# Source.net
KiCad netlist of a schematic drawn in Altium Designer
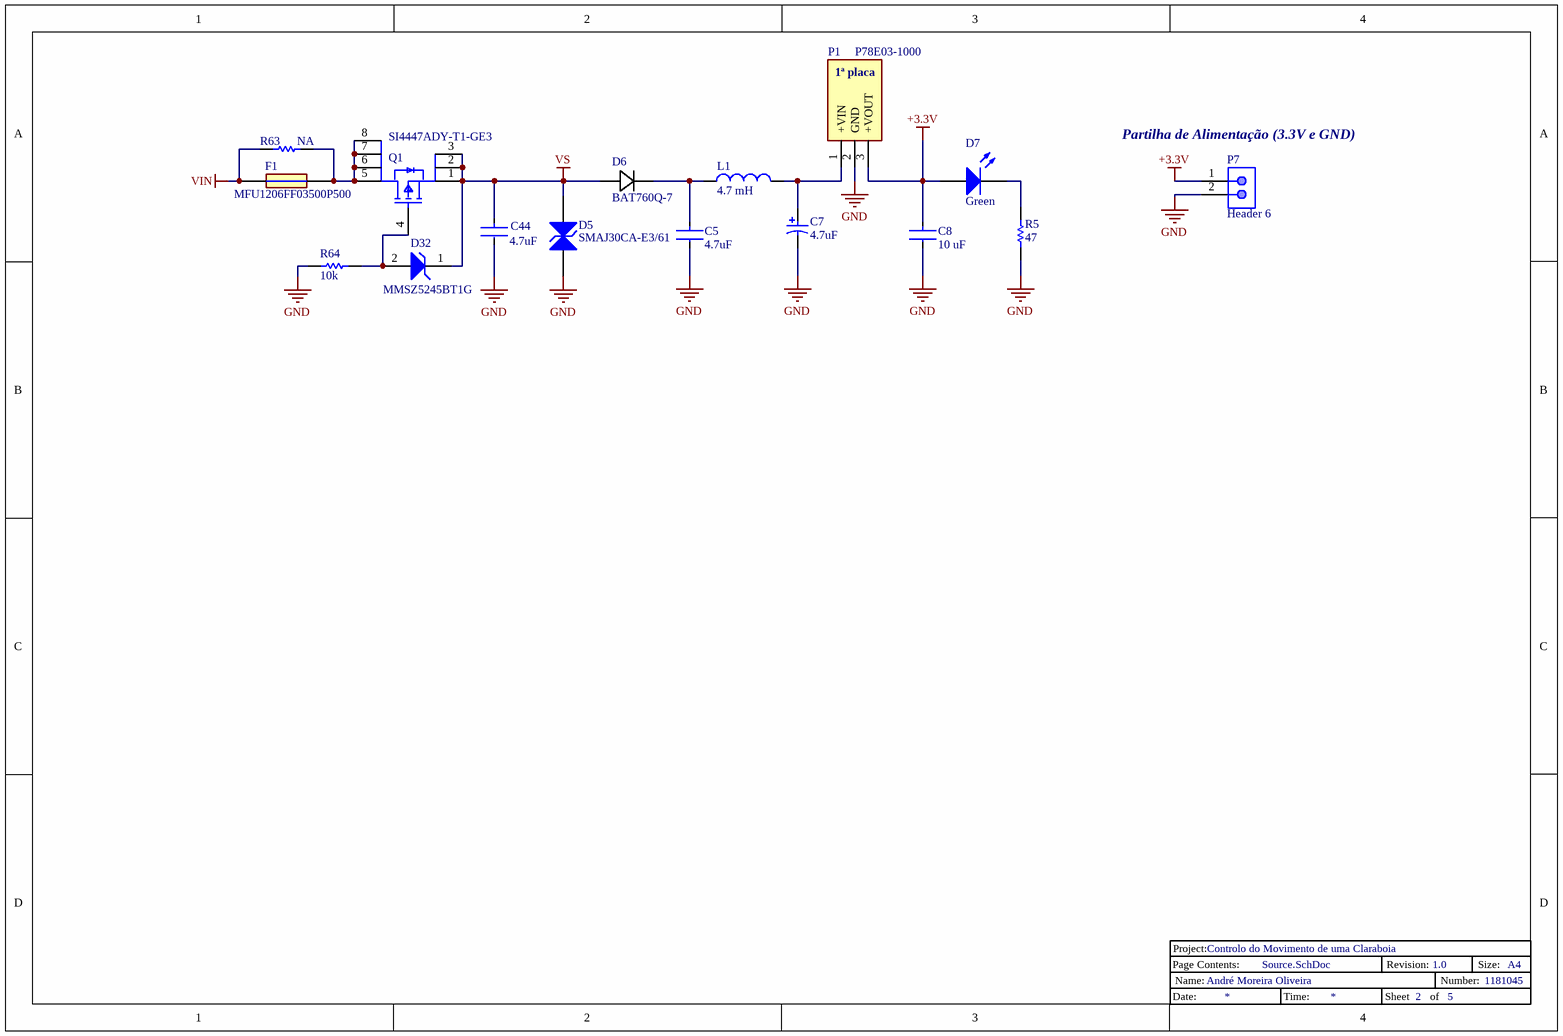
[diagram p0: Source.SchDoc]

(export (version "E")
  (design (tool "Eeschema 10.0.6"))
  (components
    (comp (ref "C5")
      (value "4.7uF")
      (footprint "FP-GRT21B-0_15-IPC_B")
      (description "Cap Ceramic 4.7uF 50V X5R ±10% SMD 0805 +85°C Emboss T/R")
      (fields (field (name "TOLERANCE") "10%"))
      (libsource (lib "Altium Content Vault") (part "11868f565c42a9108669ba33697ecf6"))
    )
    (comp (ref "C7")
      (value "4.7uF")
      (footprint "KEMT-T491-D_L")
      (fields (field (name "VOLTAGE") "50VDC") (field (name "MANUFACTURER") "Kemet"))
      (libsource (lib "Altium Content Vault") (part "CAP-P-2"))
    )
    (comp (ref "C8")
      (value "10 uF")
      (footprint "FP-GRM21B-0_2-e0_2_0_7-IPC_C")
      (libsource (lib "Altium Content Vault") (part "b4654b650e69147ec39a6b967a45e02"))
    )
    (comp (ref "C44")
      (value "4.7uF")
      (footprint "FP-GRT21B-0_15-IPC_B")
      (description "Cap Ceramic 4.7uF 50V X5R ±10% SMD 0805 +85°C Emboss T/R")
      (fields (field (name "TOLERANCE") "10%"))
      (libsource (lib "Altium Content Vault") (part "11868f565c42a9108669ba33697ecf6"))
    )
    (comp (ref "D5")
      (value "SMAJ30CA-E3/61")
      (footprint "VISH-DO-214AC-2_L")
      (fields (field (name "MANUFACTURER") "Vishay Semiconductor"))
      (libsource (lib "Altium Content Vault") (part "VISH-A1A2-2"))
    )
    (comp (ref "D6")
      (value "BAT760Q-7")
      (footprint "DIODE_SOD-323_1P7X1P3_DIO-L")
      (description "No Description Available")
      (fields (field (name "COPYRIGHT") "Copyright (C) 2018 Accelerated Designs. All rights reserved"))
      (libsource (lib "BAT760Q-7") (part "BAT760Q-7"))
    )
    (comp (ref "D7")
      (value "Green")
      (footprint "0805_A")
      (description "SMD mono-color Chip LED, WL-SMCW, Bright Green")
      (fields (field (name "PARTNUMBER") "150080VS75000") (field (name "MANUFACTURER") "Wuerth Elektronik"))
      (libsource (lib "Altium Content Vault") (part "WE-LED_K1A2-2"))
    )
    (comp (ref "D32")
      (value "MMSZ5245BT1G")
      (footprint "ONSC-SOD-123-2-425-04_V")
      (description "Zener Voltage Regulator, 500 mW, 2-Pin SOD-123, Pb-Free, Tape and Reel")
      (fields (field (name "MANUFACTURER") "On Semiconductor"))
      (libsource (lib "Altium Content Vault") (part "ONSC-K1A2-2"))
    )
    (comp (ref "F1")
      (value "MFU1206FF03500P500")
      (footprint "SamacSys:RESC3216X65N")
      (description "Fuse")
      (fields
        (field (name "MANUFACTURER_PART_NUMBER") "MFU1206FF00500P100")
        (field (name "MOUSER PART NUMBER") "594-MFU1206FF00500P1")
      )
      (libsource (lib "*") (part "MFU1206FF00500P100"))
    )
    (comp (ref "L1")
      (value "4.7 mH")
      (footprint "WE-TI-LM")
      (description "Radial Leaded Wire Wound Inductor WE-TI, L = 4700 µH 7447721047")
      (libsource (lib "Altium Content Vault") (part "PAS-IND-INDUCTOR-2"))
    )
    (comp (ref "P1")
      (value "P78E03-1000")
      (footprint "SamacSys:P78E031000")
      (description "Connector")
      (fields (field (name "MOUSER PART NUMBER") "490-P78E03-1000"))
      (libsource (lib "*") (part "P78E03-1000"))
    )
    (comp (ref "P7")
      (value "Header 6")
      (footprint "MOLX-22-27-2021_V")
      (fields (field (name "MANUFACTURER") "Molex") (field (name "PARTNUMBER") "0022272021"))
      (libsource (lib "Altium Content Vault") (part "CN-1P-M-R2"))
    )
    (comp (ref "Q1")
      (value "SI4447ADY-T1-GE3")
      (footprint "FP-C-06527-MFG")
      (description "MOSFET P-CH 40V 7.2A 8SOIC")
      (fields
        (field (name "MANUFACTURER") "Vishay")
        (field (name "OCTOPART") "https://octopart.com/si4447ady-t1-ge3-vishay-44677033")
      )
      (libsource (lib "Altium Content Vault") (part "3e6ef26ae044604f9a28074748c896e"))
    )
    (comp (ref "R5")
      (value "47")
      (footprint "RESC1608X55X30NL20T20")
      (fields (field (name "PART NUMBER") "ERA3AEB470V") (field (name "MANUFACTURER") "Panasonic"))
      (libsource (lib "Altium Content Vault") (part "RES"))
    )
    (comp (ref "R63")
      (value "NA")
      (footprint "RESC1608X55X25ML10T15")
      (description "Chip Resistor, 0 Ohm, +/- 5%, 0.1 W, -55 to 155 degC, 0603 (1608 Metric), RoHS, Tape and Reel")
      (fields (field (name "TOLERANCE") "5%") (field (name "MANUFACTURER") "Yageo"))
      (libsource (lib "") (part "RES-2_1"))
    )
    (comp (ref "R64")
      (value "10k")
      (footprint "RESC1608X55X25ML10T15")
      (description "Resistor, 10 kOhm, +/- 5%, 100 mW, -55 to 155 degC, 0603 (1608 Metric), RoHS, Tape and Reel")
      (fields (field (name "MANUFACTURER") "Yageo") (field (name "TOLERANCE") "5%"))
      (libsource (lib "Altium Content Vault") (part "RES-2"))
    )
    (comp (ref "Title_Block_2") (value "Title_Block") (libsource (lib "Title_Block") (part "Title_Block")))
  )
  (nets
    (net (code "1") (name "+3.3V") (class "Default")
      (node (ref "C8") (pin "1") (pinfunction "1_1") (pintype "passive"))
      (node (ref "D7") (pin "2") (pinfunction "A_2") (pintype "passive"))
      (node (ref "P1") (pin "3") (pinfunction "+VOUT_3") (pintype "passive"))
      (node (ref "P7") (pin "1") (pinfunction "1_1") (pintype "passive"))
    )
    (net (code "2") (name "GND") (class "Default")
      (node (ref "C44") (pin "2") (pinfunction "2_2") (pintype "passive"))
      (node (ref "C5") (pin "2") (pinfunction "2_2") (pintype "passive"))
      (node (ref "C7") (pin "2") (pinfunction "2_2") (pintype "passive"))
      (node (ref "C8") (pin "2") (pinfunction "2_2") (pintype "passive"))
      (node (ref "D5") (pin "2") (pinfunction "A2_2") (pintype "passive"))
      (node (ref "P1") (pin "2") (pinfunction "GND_2") (pintype "passive"))
      (node (ref "P7") (pin "2") (pinfunction "2_2") (pintype "passive"))
      (node (ref "R5") (pin "1") (pinfunction "1_1") (pintype "passive"))
      (node (ref "R64") (pin "1") (pinfunction "1_1") (pintype "passive"))
    )
    (net (code "3") (name "Net-(C5-Pad1)") (class "Default")
      (node (ref "C5") (pin "1") (pinfunction "1_1") (pintype "passive"))
      (node (ref "D6") (pin "1") (pinfunction "1_1") (pintype "passive"))
      (node (ref "L1") (pin "1") (pinfunction "1_1") (pintype "passive"))
    )
    (net (code "4") (name "Net-(D7-K)") (class "Default")
      (node (ref "D7") (pin "1") (pinfunction "K_1") (pintype "passive"))
      (node (ref "R5") (pin "2") (pinfunction "2_2") (pintype "passive"))
    )
    (net (code "5") (name "Net-(D32-A)") (class "Default")
      (node (ref "D32") (pin "2") (pinfunction "A_2") (pintype "passive"))
      (node (ref "Q1") (pin "4") (pinfunction "G_4") (pintype "passive"))
      (node (ref "R64") (pin "2") (pinfunction "2_2") (pintype "passive"))
    )
    (net (code "6") (name "Net-(F1-Pad2)") (class "Default")
      (node (ref "F1") (pin "2") (pinfunction "2_2") (pintype "passive"))
      (node (ref "Q1") (pin "5") (pinfunction "D_5") (pintype "passive"))
      (node (ref "Q1") (pin "6") (pinfunction "D_6") (pintype "passive"))
      (node (ref "Q1") (pin "7") (pinfunction "D_7") (pintype "passive"))
      (node (ref "Q1") (pin "8") (pinfunction "D_8") (pintype "passive"))
      (node (ref "R63") (pin "2") (pinfunction "2_2") (pintype "passive"))
    )
    (net (code "7") (name "Net-(P1-+VIN)") (class "Default")
      (node (ref "C7") (pin "1") (pinfunction "1_1") (pintype "passive"))
      (node (ref "L1") (pin "2") (pinfunction "2_2") (pintype "passive"))
      (node (ref "P1") (pin "1") (pinfunction "+VIN_1") (pintype "passive"))
    )
    (net (code "8") (name "VIN") (class "Default")
      (node (ref "F1") (pin "1") (pinfunction "1_1") (pintype "passive"))
      (node (ref "R63") (pin "1") (pinfunction "1_1") (pintype "passive"))
    )
    (net (code "9") (name "VS") (class "Default")
      (node (ref "C44") (pin "1") (pinfunction "1_1") (pintype "passive"))
      (node (ref "D32") (pin "1") (pinfunction "K_1") (pintype "passive"))
      (node (ref "D5") (pin "1") (pinfunction "A1_1") (pintype "passive"))
      (node (ref "D6") (pin "2") (pinfunction "2_2") (pintype "passive"))
      (node (ref "Q1") (pin "1") (pinfunction "S_1") (pintype "passive"))
      (node (ref "Q1") (pin "2") (pinfunction "S_2") (pintype "passive"))
      (node (ref "Q1") (pin "3") (pinfunction "S_3") (pintype "passive"))
    )
  )
)
